# M.net
KiCad netlist of a schematic drawn in Altium Designer
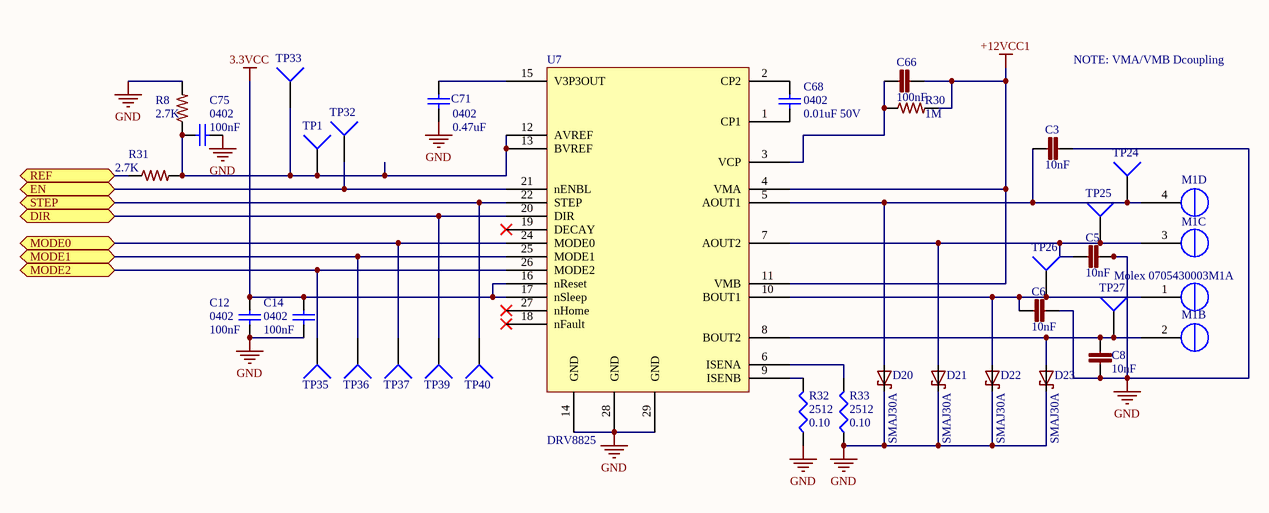
[diagram p0: M.SchDoc]

(export (version "E")
  (design (tool "Eeschema 10.0.6"))
  (components
    (comp (ref "C3")
      (value "10nF")
      (footprint "C0603")
      (description "CAP CER 0603 10nF 25V 10% X7R")
      (fields
        (field (name "MANUFACTURERPARTNUMBER") "C1608X7R1E103K080AA")
        (field (name "PUBLISHER") "UltiMachine")
      )
      (libsource (lib "") (part "C1608X7R1E103K080AA_1"))
    )
    (comp (ref "C5")
      (value "10nF")
      (footprint "C0603")
      (description "CAP CER 0603 10nF 25V 10% X7R")
      (fields
        (field (name "MANUFACTURERPARTNUMBER") "C1608X7R1E103K080AA")
        (field (name "PUBLISHER") "UltiMachine")
      )
      (libsource (lib "") (part "C1608X7R1E103K080AA_1"))
    )
    (comp (ref "C6")
      (value "10nF")
      (footprint "C0603")
      (description "CAP CER 0603 10nF 25V 10% X7R")
      (fields
        (field (name "MANUFACTURERPARTNUMBER") "C1608X7R1E103K080AA")
        (field (name "PUBLISHER") "UltiMachine")
      )
      (libsource (lib "") (part "C1608X7R1E103K080AA_1"))
    )
    (comp (ref "C8")
      (value "10nF")
      (footprint "C0603")
      (description "CAP CER 0603 10nF 25V 10% X7R")
      (fields
        (field (name "MANUFACTURERPARTNUMBER") "C1608X7R1E103K080AA")
        (field (name "PUBLISHER") "UltiMachine")
      )
      (libsource (lib "3Delight") (part "C1608X7R1E103K080AA"))
    )
    (comp (ref "C12")
      (value "100nF")
      (footprint "C0402")
      (description "Capacitor (Semiconductor SIM Model)")
      (fields
        (field (name "MFR PART #") "GRM155R71C104KA88D")
        (field (name "MFR") "Murata")
        (field (name "PACKAGEREFERENCE") "0402")
        (field (name "PUBLISHER") "Ultimachine")
      )
      (libsource (lib "Tigershark3D") (part "100nF C0402 - GRM155R71C104KA88D"))
    )
    (comp (ref "C14")
      (value "100nF")
      (footprint "C0402")
      (description "Capacitor (Semiconductor SIM Model)")
      (fields
        (field (name "MFR PART #") "GRM155R71C104KA88D")
        (field (name "MFR") "Murata")
        (field (name "PACKAGEREFERENCE") "0402")
        (field (name "PUBLISHER") "Ultimachine")
      )
      (libsource (lib "Tigershark3D") (part "100nF C0402 - GRM155R71C104KA88D"))
    )
    (comp (ref "C66")
      (value "100nF")
      (footprint "C0603")
      (description "CAP CER 0603 100nF 50V 10% X7R")
      (fields
        (field (name "MANUFACTURERPARTNUMBER") "C0603C104K5RACTU")
        (field (name "PUBLISHER") "UltiMachine")
      )
      (libsource (lib "3Delight") (part "C0603C104K5RACTU"))
    )
    (comp (ref "C68")
      (value "0.01uF 50V")
      (footprint "C0402")
      (description "CAP CER 10000PF 50V X7R 0402")
      (fields
        (field (name "MFR PART #") "GRM155R71H103JA88D")
        (field (name "MFR") "Murata")
        (field (name "PACKAGEREFERENCE") "0402")
        (field (name "PUBLISHER") "Ultimachine")
      )
      (libsource (lib "Tigershark3D") (part "GRM155R71H103JA88D"))
    )
    (comp (ref "C71")
      (value "0.47uF")
      (footprint "C0402")
      (description "0.47uF 6.3v C0402 - GRM155R60J474KE19D")
      (fields
        (field (name "MFR PART #") "GRM155R60J474KE19D")
        (field (name "MFR") "Murata")
        (field (name "PACKAGEREFERENCE") "0402")
        (field (name "PUBLISHER") "Ultimachine")
      )
      (libsource (lib "Tigershark3D") (part "GRM155R60J474KE19D"))
    )
    (comp (ref "C75")
      (value "100nF")
      (footprint "C0402")
      (description "Capacitor (Semiconductor SIM Model)")
      (fields
        (field (name "MFR PART #") "GRM155R71C104KA88D")
        (field (name "MFR") "Murata")
        (field (name "PACKAGEREFERENCE") "0402")
        (field (name "PUBLISHER") "Ultimachine")
      )
      (libsource (lib "Tigershark3D") (part "100nF C0402 - GRM155R71C104KA88D"))
    )
    (comp (ref "D20")
      (value "SMAJ30A")
      (footprint "SMA-SM")
      (description "DIODE TVS 30V SMA")
      (fields (field (name "PUBLISHER") "UltiMachine"))
      (libsource (lib "Tigershark3D") (part "SMAJ30A"))
    )
    (comp (ref "D21")
      (value "SMAJ30A")
      (footprint "SMA-SM")
      (description "DIODE TVS 30V SMA")
      (fields (field (name "PUBLISHER") "UltiMachine"))
      (libsource (lib "Tigershark3D") (part "SMAJ30A"))
    )
    (comp (ref "D22")
      (value "SMAJ30A")
      (footprint "SMA-SM")
      (description "DIODE TVS 30V SMA")
      (fields (field (name "PUBLISHER") "UltiMachine"))
      (libsource (lib "Tigershark3D") (part "SMAJ30A"))
    )
    (comp (ref "D23")
      (value "SMAJ30A")
      (footprint "SMA-SM")
      (description "DIODE TVS 30V SMA")
      (fields (field (name "PUBLISHER") "UltiMachine"))
      (libsource (lib "Tigershark3D") (part "SMAJ30A"))
    )
    (comp (ref "M1")
      (value "Molex 0705430003")
      (footprint "4POL254")
      (description "Molex 4 Pin Clip Connector")
      (libsource (lib "ZMBo Schematic Library") (part "Molex 0705430003 Alt"))
    )
    (comp (ref "R8")
      (value "2.7K")
      (footprint "R0402")
      (description "RES SMD 2.7K OHM 1% 1/10W 0402")
      (fields
        (field (name "MANUFACTURER") "Panasonic")
        (field (name "MANUFACTURERPARTNUMBER") "ERJ2GEJ105X")
        (field (name "PUBLISHER") "Adam")
      )
      (libsource (lib "Tigershark3D") (part "ERJ-2RKF2701X"))
    )
    (comp (ref "R30")
      (value "1M")
      (footprint "R0402")
      (description "RES 0402 1M 100mW 5%")
      (fields (field (name "MANUFACTURERPARTNUMBER") "ERJ2GEJ105X") (field (name "PUBLISHER") "UltiMachine"))
      (libsource (lib "Tigershark3D") (part "ERJ2GEJ105X"))
    )
    (comp (ref "R31")
      (value "2.7K")
      (footprint "R0402")
      (description "RES SMD 2.7K OHM 1% 1/10W 0402")
      (fields
        (field (name "MANUFACTURER") "Panasonic")
        (field (name "MANUFACTURERPARTNUMBER") "ERJ2GEJ105X")
        (field (name "PUBLISHER") "Adam")
      )
      (libsource (lib "Tigershark3D") (part "ERJ-2RKF2701X"))
    )
    (comp (ref "R32")
      (value "2512")
      (footprint "2512R-0.55")
      (description "RES SMD 0.1 OHM 1% 2W 2512")
      (fields (field (name "MFR") "Stackpole ELectronics Inc") (field (name "ALTIUM_VALUE") "0.10"))
      (libsource (lib "Tigershark3D") (part "CSRN2512FTR100"))
    )
    (comp (ref "R33")
      (value "2512")
      (footprint "2512R-0.55")
      (description "RES SMD 0.1 OHM 1% 2W 2512")
      (fields (field (name "MFR") "Stackpole ELectronics Inc") (field (name "ALTIUM_VALUE") "0.10"))
      (libsource (lib "Tigershark3D") (part "CSRN2512FTR100"))
    )
    (comp (ref "TP1")
      (value "TP4")
      (footprint "TP-2")
      (description "Socket")
      (fields (field (name "PUBLISHER") "Altium Limited"))
      (libsource (lib "ZMBo Schematic Library") (part "Socket"))
    )
    (comp (ref "TP24")
      (value "TP4")
      (footprint "TP-2")
      (description "Socket")
      (fields (field (name "PUBLISHER") "Altium Limited"))
      (libsource (lib "ZMBo Schematic Library") (part "Socket"))
    )
    (comp (ref "TP25")
      (value "TP4")
      (footprint "TP-2")
      (description "Socket")
      (fields (field (name "PUBLISHER") "Altium Limited"))
      (libsource (lib "ZMBo Schematic Library") (part "Socket"))
    )
    (comp (ref "TP26")
      (value "TP4")
      (footprint "TP-2")
      (description "Socket")
      (fields (field (name "PUBLISHER") "Altium Limited"))
      (libsource (lib "ZMBo Schematic Library") (part "Socket"))
    )
    (comp (ref "TP27")
      (value "TP4")
      (footprint "TP-2")
      (description "Socket")
      (fields (field (name "PUBLISHER") "Altium Limited"))
      (libsource (lib "ZMBo Schematic Library") (part "Socket"))
    )
    (comp (ref "TP32")
      (value "TP4")
      (footprint "TP-2")
      (description "Socket")
      (fields (field (name "PUBLISHER") "Altium Limited"))
      (libsource (lib "ZMBo Schematic Library") (part "Socket"))
    )
    (comp (ref "TP33")
      (value "TP4")
      (footprint "TP-2")
      (description "Socket")
      (fields (field (name "PUBLISHER") "Altium Limited"))
      (libsource (lib "ZMBo Schematic Library") (part "Socket"))
    )
    (comp (ref "TP35")
      (value "TP4")
      (footprint "TP-2")
      (description "Socket")
      (fields (field (name "PUBLISHER") "Altium Limited"))
      (libsource (lib "ZMBo Schematic Library") (part "Socket"))
    )
    (comp (ref "TP36")
      (value "TP4")
      (footprint "TP-2")
      (description "Socket")
      (fields (field (name "PUBLISHER") "Altium Limited"))
      (libsource (lib "ZMBo Schematic Library") (part "Socket"))
    )
    (comp (ref "TP37")
      (value "TP4")
      (footprint "TP-2")
      (description "Socket")
      (fields (field (name "PUBLISHER") "Altium Limited"))
      (libsource (lib "ZMBo Schematic Library") (part "Socket"))
    )
    (comp (ref "TP39")
      (value "TP4")
      (footprint "TP-2")
      (description "Socket")
      (fields (field (name "PUBLISHER") "Altium Limited"))
      (libsource (lib "ZMBo Schematic Library") (part "Socket"))
    )
    (comp (ref "TP40")
      (value "TP4")
      (footprint "TP-2")
      (description "Socket")
      (fields (field (name "PUBLISHER") "Altium Limited"))
      (libsource (lib "ZMBo Schematic Library") (part "Socket"))
    )
    (comp (ref "U7")
      (value "DRV8825")
      (footprint "DRV8825PWPR")
      (description "DRV8825 Ti Stepper Driver")
      (fields (field (name "PART NUMBER") "DRV8825PWPR") (field (name "VOLTAGE") "8.2-45VDC"))
      (libsource (lib "Tigershark3D") (part "DRV8825"))
    )
  )
  (nets
    (net (code "1") (name "+12VCC1") (class "Default")
      (node (ref "C66") (pin "2") (pinfunction "2_2") (pintype "passive"))
      (node (ref "R30") (pin "2") (pinfunction "2_2") (pintype "passive"))
      (node (ref "U7") (pin "11") (pinfunction "VMB_11") (pintype "passive"))
      (node (ref "U7") (pin "4") (pinfunction "VMA_4") (pintype "passive"))
    )
    (net (code "2") (name "/DIR") (class "Default")
      (node (ref "TP39") (pin "1") (pinfunction "1_1") (pintype "passive"))
      (node (ref "U7") (pin "20") (pinfunction "DIR_20") (pintype "passive"))
    )
    (net (code "3") (name "/EN") (class "Default")
      (node (ref "TP32") (pin "1") (pinfunction "1_1") (pintype "passive"))
      (node (ref "U7") (pin "21") (pinfunction "nENBL_21") (pintype "passive"))
    )
    (net (code "4") (name "/MODE0") (class "Default")
      (node (ref "TP37") (pin "1") (pinfunction "1_1") (pintype "passive"))
      (node (ref "U7") (pin "24") (pinfunction "MODE0_24") (pintype "passive"))
    )
    (net (code "5") (name "/MODE1") (class "Default")
      (node (ref "TP36") (pin "1") (pinfunction "1_1") (pintype "passive"))
      (node (ref "U7") (pin "25") (pinfunction "MODE1_25") (pintype "passive"))
    )
    (net (code "6") (name "/MODE2") (class "Default")
      (node (ref "TP35") (pin "1") (pinfunction "1_1") (pintype "passive"))
      (node (ref "U7") (pin "26") (pinfunction "MODE2_26") (pintype "passive"))
    )
    (net (code "7") (name "/REF") (class "Default")
      (node (ref "R31") (pin "1") (pinfunction "1_1") (pintype "passive"))
    )
    (net (code "8") (name "/STEP") (class "Default")
      (node (ref "TP40") (pin "1") (pinfunction "1_1") (pintype "passive"))
      (node (ref "U7") (pin "22") (pinfunction "STEP_22") (pintype "passive"))
    )
    (net (code "9") (name "3.3VCC") (class "Default")
      (node (ref "C12") (pin "2") (pinfunction "2_2") (pintype "passive"))
      (node (ref "C14") (pin "2") (pinfunction "2_2") (pintype "passive"))
      (node (ref "U7") (pin "16") (pinfunction "nReset_16") (pintype "passive"))
      (node (ref "U7") (pin "17") (pinfunction "nSleep_17") (pintype "passive"))
    )
    (net (code "10") (name "GND") (class "Default")
      (node (ref "C12") (pin "1") (pinfunction "1_1") (pintype "passive"))
      (node (ref "C14") (pin "1") (pinfunction "1_1") (pintype "passive"))
      (node (ref "C3") (pin "2") (pinfunction "2_2") (pintype "passive"))
      (node (ref "C5") (pin "2") (pinfunction "2_2") (pintype "passive"))
      (node (ref "C6") (pin "2") (pinfunction "2_2") (pintype "passive"))
      (node (ref "C71") (pin "1") (pinfunction "1_1") (pintype "passive"))
      (node (ref "C75") (pin "1") (pinfunction "1_1") (pintype "passive"))
      (node (ref "C8") (pin "1") (pinfunction "1_1") (pintype "passive"))
      (node (ref "D20") (pin "C") (pinfunction "C_C") (pintype "passive"))
      (node (ref "D21") (pin "C") (pinfunction "C_C") (pintype "passive"))
      (node (ref "D22") (pin "C") (pinfunction "C_C") (pintype "passive"))
      (node (ref "D23") (pin "C") (pinfunction "C_C") (pintype "passive"))
      (node (ref "R32") (pin "1") (pinfunction "1_1") (pintype "passive"))
      (node (ref "R33") (pin "1") (pinfunction "1_1") (pintype "passive"))
      (node (ref "R8") (pin "2") (pinfunction "2_2") (pintype "passive"))
      (node (ref "U7") (pin "14") (pinfunction "GND_14") (pintype "passive"))
      (node (ref "U7") (pin "28") (pinfunction "GND_28") (pintype "passive"))
      (node (ref "U7") (pin "29") (pinfunction "GND_29") (pintype "passive"))
    )
    (net (code "11") (name "Net-(M1A-OUT2B)") (class "Default")
      (node (ref "C6") (pin "1") (pinfunction "1_1") (pintype "passive"))
      (node (ref "D22") (pin "A") (pinfunction "A_A") (pintype "passive"))
      (node (ref "M1") (pin "1") (pinfunction "OUT2B_1") (pintype "passive"))
      (node (ref "TP26") (pin "1") (pinfunction "1_1") (pintype "passive"))
      (node (ref "U7") (pin "10") (pinfunction "BOUT1_10") (pintype "passive"))
    )
    (net (code "12") (name "Net-(M1B-OUT2A)") (class "Default")
      (node (ref "C8") (pin "2") (pinfunction "2_2") (pintype "passive"))
      (node (ref "D23") (pin "A") (pinfunction "A_A") (pintype "passive"))
      (node (ref "M1") (pin "2") (pinfunction "OUT2A_2") (pintype "passive"))
      (node (ref "TP27") (pin "1") (pinfunction "1_1") (pintype "passive"))
      (node (ref "U7") (pin "8") (pinfunction "BOUT2_8") (pintype "passive"))
    )
    (net (code "13") (name "Net-(M1C-OUT1A)") (class "Default")
      (node (ref "C5") (pin "1") (pinfunction "1_1") (pintype "passive"))
      (node (ref "D21") (pin "A") (pinfunction "A_A") (pintype "passive"))
      (node (ref "M1") (pin "3") (pinfunction "OUT1A_3") (pintype "passive"))
      (node (ref "TP25") (pin "1") (pinfunction "1_1") (pintype "passive"))
      (node (ref "U7") (pin "7") (pinfunction "AOUT2_7") (pintype "passive"))
    )
    (net (code "14") (name "Net-(M1D-OUT1B)") (class "Default")
      (node (ref "C3") (pin "1") (pinfunction "1_1") (pintype "passive"))
      (node (ref "D20") (pin "A") (pinfunction "A_A") (pintype "passive"))
      (node (ref "M1") (pin "4") (pinfunction "OUT1B_4") (pintype "passive"))
      (node (ref "TP24") (pin "1") (pinfunction "1_1") (pintype "passive"))
      (node (ref "U7") (pin "5") (pinfunction "AOUT1_5") (pintype "passive"))
    )
    (net (code "15") (name "Net-(U7-AVREF)") (class "Default")
      (node (ref "C75") (pin "2") (pinfunction "2_2") (pintype "passive"))
      (node (ref "R31") (pin "2") (pinfunction "2_2") (pintype "passive"))
      (node (ref "R8") (pin "1") (pinfunction "1_1") (pintype "passive"))
      (node (ref "TP1") (pin "1") (pinfunction "1_1") (pintype "passive"))
      (node (ref "TP33") (pin "1") (pinfunction "1_1") (pintype "passive"))
      (node (ref "U7") (pin "12") (pinfunction "AVREF_12") (pintype "passive"))
      (node (ref "U7") (pin "13") (pinfunction "BVREF_13") (pintype "passive"))
    )
    (net (code "16") (name "Net-(U7-CP1)") (class "Default")
      (node (ref "C68") (pin "1") (pinfunction "1_1") (pintype "passive"))
      (node (ref "U7") (pin "1") (pinfunction "CP1_1") (pintype "passive"))
    )
    (net (code "17") (name "Net-(U7-CP2)") (class "Default")
      (node (ref "C68") (pin "2") (pinfunction "2_2") (pintype "passive"))
      (node (ref "U7") (pin "2") (pinfunction "CP2_2") (pintype "passive"))
    )
    (net (code "18") (name "Net-(U7-ISENA)") (class "Default")
      (node (ref "R33") (pin "2") (pinfunction "2_2") (pintype "passive"))
      (node (ref "U7") (pin "6") (pinfunction "ISENA_6") (pintype "passive"))
    )
    (net (code "19") (name "Net-(U7-ISENB)") (class "Default")
      (node (ref "R32") (pin "2") (pinfunction "2_2") (pintype "passive"))
      (node (ref "U7") (pin "9") (pinfunction "ISENB_9") (pintype "passive"))
    )
    (net (code "20") (name "Net-(U7-V3P3OUT)") (class "Default")
      (node (ref "C71") (pin "2") (pinfunction "2_2") (pintype "passive"))
      (node (ref "U7") (pin "15") (pinfunction "V3P3OUT_15") (pintype "passive"))
    )
    (net (code "21") (name "Net-(U7-VCP)") (class "Default")
      (node (ref "C66") (pin "1") (pinfunction "1_1") (pintype "passive"))
      (node (ref "R30") (pin "1") (pinfunction "1_1") (pintype "passive"))
      (node (ref "U7") (pin "3") (pinfunction "VCP_3") (pintype "passive"))
    )
    (net (code "22") (name "unconnected-(U7-DECAY-Pad19)") (class "Default")
      (node (ref "U7") (pin "19") (pinfunction "DECAY_19") (pintype "passive+no_connect"))
    )
    (net (code "23") (name "unconnected-(U7-NC-Pad23)") (class "Default")
      (node (ref "U7") (pin "23") (pinfunction "NC_23") (pintype "passive"))
    )
    (net (code "24") (name "unconnected-(U7-nFault-Pad18)") (class "Default")
      (node (ref "U7") (pin "18") (pinfunction "nFault_18") (pintype "passive+no_connect"))
    )
    (net (code "25") (name "unconnected-(U7-nHome-Pad27)") (class "Default")
      (node (ref "U7") (pin "27") (pinfunction "nHome_27") (pintype "passive+no_connect"))
    )
  )
)
